# LDAQ-MOD-BREADBOARD.net
KiCad netlist of a schematic drawn in EAGLE
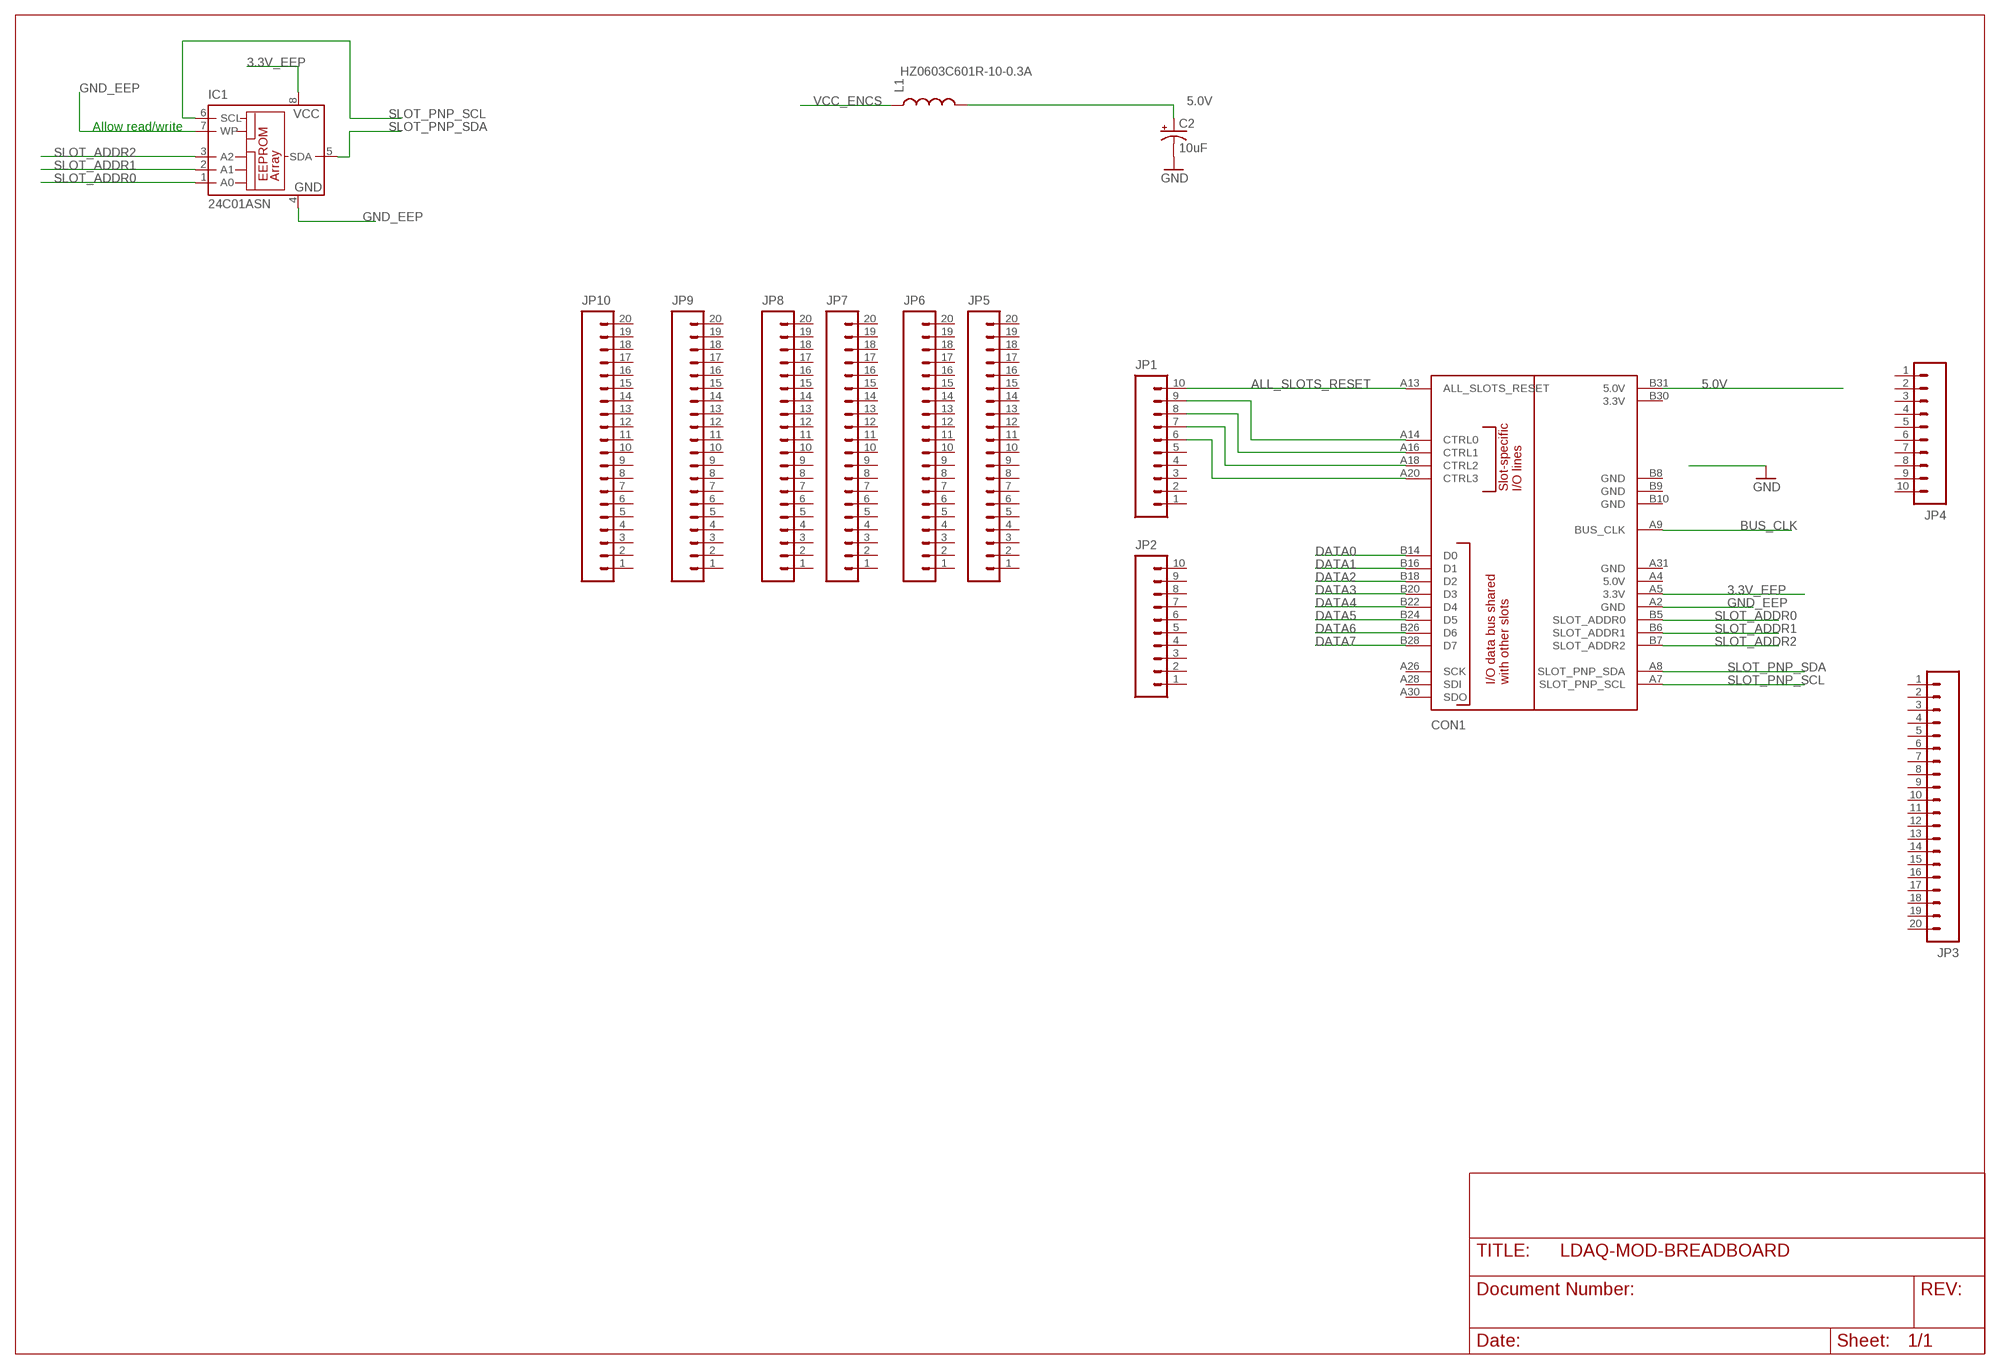
[diagram p0: schematic, sheet 1]

(export (version "E")
  (design (tool "Eeschema 10.0.6"))
  (components
    (comp (ref "C2")
      (value "10uF")
      (footprint "eagle-import:EIA3216")
      (libsource (lib "eagle-import") (part "CAP_POL1206"))
    )
    (comp (ref "CON1")
      (value "BOARD")
      (footprint "eagle-import:PCI-E_64_EDGE_70X60")
      (libsource (lib "eagle-import") (part "LIBREDAQ_DAUGHTER_BOARDPCIE-64_SIZE1"))
    )
    (comp (ref "IC1")
      (value "24C01ASN")
      (footprint "eagle-import:SO-08")
      (fields (field (name "MPN") "AT24C01BN-SH-B"))
      (libsource (lib "eagle-import") (part "24CSN01A"))
    )
    (comp (ref "JP1")
      (value "M10NO_SILK_PTH_FEMALE")
      (footprint "eagle-import:1X10_NO_SILK")
      (libsource (lib "eagle-import") (part "M10NO_SILK_PTH_FEMALE"))
    )
    (comp (ref "JP2")
      (value "M10NO_SILK_PTH_FEMALE")
      (footprint "eagle-import:1X10_NO_SILK")
      (libsource (lib "eagle-import") (part "M10NO_SILK_PTH_FEMALE"))
    )
    (comp (ref "JP3")
      (value "M20")
      (footprint "eagle-import:1X20")
      (libsource (lib "eagle-import") (part "M20"))
    )
    (comp (ref "JP4")
      (value "M10NO_SILK_PTH_FEMALE")
      (footprint "eagle-import:1X10_NO_SILK")
      (libsource (lib "eagle-import") (part "M10NO_SILK_PTH_FEMALE"))
    )
    (comp (ref "JP5")
      (value "M20")
      (footprint "eagle-import:1X20")
      (libsource (lib "eagle-import") (part "M20"))
    )
    (comp (ref "JP6")
      (value "M20")
      (footprint "eagle-import:1X20")
      (libsource (lib "eagle-import") (part "M20"))
    )
    (comp (ref "JP7")
      (value "M20")
      (footprint "eagle-import:1X20")
      (libsource (lib "eagle-import") (part "M20"))
    )
    (comp (ref "JP8")
      (value "M20")
      (footprint "eagle-import:1X20")
      (libsource (lib "eagle-import") (part "M20"))
    )
    (comp (ref "JP9")
      (value "M20")
      (footprint "eagle-import:1X20")
      (libsource (lib "eagle-import") (part "M20"))
    )
    (comp (ref "JP10")
      (value "M20")
      (footprint "eagle-import:1X20")
      (libsource (lib "eagle-import") (part "M20"))
    )
    (comp (ref "L1")
      (value "HZ0603C601R-10-0.3A")
      (footprint "eagle-import:0603")
      (libsource (lib "eagle-import") (part "INDUCTOR0603"))
    )
  )
  (nets
    (net (code "1") (name "/3.3V_EEP") (class "Default")
      (node (ref "CON1") (pin "A5") (pinfunction "3.3V_A5") (pintype "bidirectional"))
      (node (ref "IC1") (pin "8") (pinfunction "VCC_8") (pintype "power_in"))
    )
    (net (code "2") (name "/5.0V") (class "Default")
      (node (ref "C2") (pin "A") (pinfunction "+_A") (pintype "passive"))
      (node (ref "CON1") (pin "B31") (pinfunction "5.0V_B31") (pintype "bidirectional"))
      (node (ref "L1") (pin "2") (pinfunction "2_2") (pintype "passive"))
    )
    (net (code "3") (name "/ALL_SLOTS_RESET") (class "Default")
      (node (ref "CON1") (pin "A13") (pinfunction "ALL_SLOTS_RESET_A13") (pintype "bidirectional"))
      (node (ref "JP1") (pin "10") (pinfunction "10_10") (pintype "passive"))
    )
    (net (code "4") (name "/BUS_CLK") (class "Default")
      (node (ref "CON1") (pin "A9") (pinfunction "BUS_CLK_A9") (pintype "bidirectional"))
    )
    (net (code "5") (name "/DATA0") (class "Default")
      (node (ref "CON1") (pin "B14") (pinfunction "D0_B14") (pintype "bidirectional"))
    )
    (net (code "6") (name "/DATA1") (class "Default")
      (node (ref "CON1") (pin "B16") (pinfunction "D1_B16") (pintype "bidirectional"))
    )
    (net (code "7") (name "/DATA2") (class "Default")
      (node (ref "CON1") (pin "B18") (pinfunction "D2_B18") (pintype "bidirectional"))
    )
    (net (code "8") (name "/DATA3") (class "Default")
      (node (ref "CON1") (pin "B20") (pinfunction "D3_B20") (pintype "bidirectional"))
    )
    (net (code "9") (name "/DATA4") (class "Default")
      (node (ref "CON1") (pin "B22") (pinfunction "D4_B22") (pintype "bidirectional"))
    )
    (net (code "10") (name "/DATA5") (class "Default")
      (node (ref "CON1") (pin "B24") (pinfunction "D5_B24") (pintype "bidirectional"))
    )
    (net (code "11") (name "/DATA6") (class "Default")
      (node (ref "CON1") (pin "B26") (pinfunction "D6_B26") (pintype "bidirectional"))
    )
    (net (code "12") (name "/DATA7") (class "Default")
      (node (ref "CON1") (pin "B28") (pinfunction "D7_B28") (pintype "bidirectional"))
    )
    (net (code "13") (name "/GND_EEP") (class "Default")
      (node (ref "CON1") (pin "A2") (pinfunction "GND_A2") (pintype "bidirectional"))
      (node (ref "IC1") (pin "4") (pinfunction "GND_4") (pintype "power_in"))
      (node (ref "IC1") (pin "7") (pinfunction "WP_7") (pintype "input"))
    )
    (net (code "14") (name "/SLOT_ADDR0") (class "Default")
      (node (ref "CON1") (pin "B5") (pinfunction "SLOT_ADDR0_B5") (pintype "bidirectional"))
      (node (ref "IC1") (pin "1") (pinfunction "A0_1") (pintype "input"))
    )
    (net (code "15") (name "/SLOT_ADDR1") (class "Default")
      (node (ref "CON1") (pin "B6") (pinfunction "SLOT_ADDR1_B6") (pintype "bidirectional"))
      (node (ref "IC1") (pin "2") (pinfunction "A1_2") (pintype "input"))
    )
    (net (code "16") (name "/SLOT_ADDR2") (class "Default")
      (node (ref "CON1") (pin "B7") (pinfunction "SLOT_ADDR2_B7") (pintype "bidirectional"))
      (node (ref "IC1") (pin "3") (pinfunction "A2_3") (pintype "input"))
    )
    (net (code "17") (name "/SLOT_PNP_SCL") (class "Default")
      (node (ref "CON1") (pin "A7") (pinfunction "SLOT_PNP_SCL_A7") (pintype "bidirectional"))
      (node (ref "IC1") (pin "6") (pinfunction "SCL_6") (pintype "input"))
    )
    (net (code "18") (name "/SLOT_PNP_SDA") (class "Default")
      (node (ref "CON1") (pin "A8") (pinfunction "SLOT_PNP_SDA_A8") (pintype "bidirectional"))
      (node (ref "IC1") (pin "5") (pinfunction "SDA_5") (pintype "bidirectional"))
    )
    (net (code "19") (name "/VCC_ENCS") (class "Default")
      (node (ref "L1") (pin "1") (pinfunction "1_1") (pintype "passive"))
    )
    (net (code "20") (name "GND") (class "Default")
      (node (ref "C2") (pin "C") (pinfunction "-_C") (pintype "passive"))
    )
    (net (code "21") (name "Net-(CON1-CTRL0)") (class "Default")
      (node (ref "CON1") (pin "A14") (pinfunction "CTRL0_A14") (pintype "bidirectional"))
      (node (ref "JP1") (pin "9") (pinfunction "9_9") (pintype "passive"))
    )
    (net (code "22") (name "Net-(CON1-CTRL1)") (class "Default")
      (node (ref "CON1") (pin "A16") (pinfunction "CTRL1_A16") (pintype "bidirectional"))
      (node (ref "JP1") (pin "8") (pinfunction "8_8") (pintype "passive"))
    )
    (net (code "23") (name "Net-(CON1-CTRL2)") (class "Default")
      (node (ref "CON1") (pin "A18") (pinfunction "CTRL2_A18") (pintype "bidirectional"))
      (node (ref "JP1") (pin "7") (pinfunction "7_7") (pintype "passive"))
    )
    (net (code "24") (name "Net-(CON1-CTRL3)") (class "Default")
      (node (ref "CON1") (pin "A20") (pinfunction "CTRL3_A20") (pintype "bidirectional"))
      (node (ref "JP1") (pin "6") (pinfunction "6_6") (pintype "passive"))
    )
    (net (code "25") (name "unconnected-(CON1-3.3V-PadB30)") (class "Default")
      (node (ref "CON1") (pin "B30") (pinfunction "3.3V_B30") (pintype "bidirectional"))
    )
    (net (code "26") (name "unconnected-(CON1-5.0V-PadA4)") (class "Default")
      (node (ref "CON1") (pin "A4") (pinfunction "5.0V_A4") (pintype "bidirectional"))
    )
    (net (code "27") (name "unconnected-(CON1-GND-PadA31)") (class "Default")
      (node (ref "CON1") (pin "A31") (pinfunction "GND_A31") (pintype "bidirectional"))
    )
    (net (code "28") (name "unconnected-(CON1-GND-PadB8)") (class "Default")
      (node (ref "CON1") (pin "B8") (pinfunction "GND_B8") (pintype "bidirectional"))
    )
    (net (code "29") (name "unconnected-(CON1-GND-PadB9)") (class "Default")
      (node (ref "CON1") (pin "B9") (pinfunction "GND_B9") (pintype "bidirectional"))
    )
    (net (code "30") (name "unconnected-(CON1-GND-PadB10)") (class "Default")
      (node (ref "CON1") (pin "B10") (pinfunction "GND_B10") (pintype "bidirectional"))
    )
    (net (code "31") (name "unconnected-(CON1-SCK-PadA26)") (class "Default")
      (node (ref "CON1") (pin "A26") (pinfunction "SCK_A26") (pintype "bidirectional"))
    )
    (net (code "32") (name "unconnected-(CON1-SDI-PadA28)") (class "Default")
      (node (ref "CON1") (pin "A28") (pinfunction "SDI_A28") (pintype "bidirectional"))
    )
    (net (code "33") (name "unconnected-(CON1-SDO-PadA30)") (class "Default")
      (node (ref "CON1") (pin "A30") (pinfunction "SDO_A30") (pintype "bidirectional"))
    )
    (net (code "34") (name "unconnected-(JP1-Pad1)") (class "Default")
      (node (ref "JP1") (pin "1") (pinfunction "1_1") (pintype "passive"))
    )
    (net (code "35") (name "unconnected-(JP1-Pad2)") (class "Default")
      (node (ref "JP1") (pin "2") (pinfunction "2_2") (pintype "passive"))
    )
    (net (code "36") (name "unconnected-(JP1-Pad3)") (class "Default")
      (node (ref "JP1") (pin "3") (pinfunction "3_3") (pintype "passive"))
    )
    (net (code "37") (name "unconnected-(JP1-Pad4)") (class "Default")
      (node (ref "JP1") (pin "4") (pinfunction "4_4") (pintype "passive"))
    )
    (net (code "38") (name "unconnected-(JP1-Pad5)") (class "Default")
      (node (ref "JP1") (pin "5") (pinfunction "5_5") (pintype "passive"))
    )
    (net (code "39") (name "unconnected-(JP2-Pad1)") (class "Default")
      (node (ref "JP2") (pin "1") (pinfunction "1_1") (pintype "passive"))
    )
    (net (code "40") (name "unconnected-(JP2-Pad2)") (class "Default")
      (node (ref "JP2") (pin "2") (pinfunction "2_2") (pintype "passive"))
    )
    (net (code "41") (name "unconnected-(JP2-Pad3)") (class "Default")
      (node (ref "JP2") (pin "3") (pinfunction "3_3") (pintype "passive"))
    )
    (net (code "42") (name "unconnected-(JP2-Pad4)") (class "Default")
      (node (ref "JP2") (pin "4") (pinfunction "4_4") (pintype "passive"))
    )
    (net (code "43") (name "unconnected-(JP2-Pad5)") (class "Default")
      (node (ref "JP2") (pin "5") (pinfunction "5_5") (pintype "passive"))
    )
    (net (code "44") (name "unconnected-(JP2-Pad6)") (class "Default")
      (node (ref "JP2") (pin "6") (pinfunction "6_6") (pintype "passive"))
    )
    (net (code "45") (name "unconnected-(JP2-Pad7)") (class "Default")
      (node (ref "JP2") (pin "7") (pinfunction "7_7") (pintype "passive"))
    )
    (net (code "46") (name "unconnected-(JP2-Pad8)") (class "Default")
      (node (ref "JP2") (pin "8") (pinfunction "8_8") (pintype "passive"))
    )
    (net (code "47") (name "unconnected-(JP2-Pad9)") (class "Default")
      (node (ref "JP2") (pin "9") (pinfunction "9_9") (pintype "passive"))
    )
    (net (code "48") (name "unconnected-(JP2-Pad10)") (class "Default")
      (node (ref "JP2") (pin "10") (pinfunction "10_10") (pintype "passive"))
    )
    (net (code "49") (name "unconnected-(JP3-Pad1)") (class "Default")
      (node (ref "JP3") (pin "1") (pinfunction "1_1") (pintype "passive"))
    )
    (net (code "50") (name "unconnected-(JP3-Pad2)") (class "Default")
      (node (ref "JP3") (pin "2") (pinfunction "2_2") (pintype "passive"))
    )
    (net (code "51") (name "unconnected-(JP3-Pad3)") (class "Default")
      (node (ref "JP3") (pin "3") (pinfunction "3_3") (pintype "passive"))
    )
    (net (code "52") (name "unconnected-(JP3-Pad4)") (class "Default")
      (node (ref "JP3") (pin "4") (pinfunction "4_4") (pintype "passive"))
    )
    (net (code "53") (name "unconnected-(JP3-Pad5)") (class "Default")
      (node (ref "JP3") (pin "5") (pinfunction "5_5") (pintype "passive"))
    )
    (net (code "54") (name "unconnected-(JP3-Pad6)") (class "Default")
      (node (ref "JP3") (pin "6") (pinfunction "6_6") (pintype "passive"))
    )
    (net (code "55") (name "unconnected-(JP3-Pad7)") (class "Default")
      (node (ref "JP3") (pin "7") (pinfunction "7_7") (pintype "passive"))
    )
    (net (code "56") (name "unconnected-(JP3-Pad8)") (class "Default")
      (node (ref "JP3") (pin "8") (pinfunction "8_8") (pintype "passive"))
    )
    (net (code "57") (name "unconnected-(JP3-Pad9)") (class "Default")
      (node (ref "JP3") (pin "9") (pinfunction "9_9") (pintype "passive"))
    )
    (net (code "58") (name "unconnected-(JP3-Pad10)") (class "Default")
      (node (ref "JP3") (pin "10") (pinfunction "10_10") (pintype "passive"))
    )
    (net (code "59") (name "unconnected-(JP3-Pad11)") (class "Default")
      (node (ref "JP3") (pin "11") (pinfunction "11_11") (pintype "passive"))
    )
    (net (code "60") (name "unconnected-(JP3-Pad12)") (class "Default")
      (node (ref "JP3") (pin "12") (pinfunction "12_12") (pintype "passive"))
    )
    (net (code "61") (name "unconnected-(JP3-Pad13)") (class "Default")
      (node (ref "JP3") (pin "13") (pinfunction "13_13") (pintype "passive"))
    )
    (net (code "62") (name "unconnected-(JP3-Pad14)") (class "Default")
      (node (ref "JP3") (pin "14") (pinfunction "14_14") (pintype "passive"))
    )
    (net (code "63") (name "unconnected-(JP3-Pad15)") (class "Default")
      (node (ref "JP3") (pin "15") (pinfunction "15_15") (pintype "passive"))
    )
    (net (code "64") (name "unconnected-(JP3-Pad16)") (class "Default")
      (node (ref "JP3") (pin "16") (pinfunction "16_16") (pintype "passive"))
    )
    (net (code "65") (name "unconnected-(JP3-Pad17)") (class "Default")
      (node (ref "JP3") (pin "17") (pinfunction "17_17") (pintype "passive"))
    )
    (net (code "66") (name "unconnected-(JP3-Pad18)") (class "Default")
      (node (ref "JP3") (pin "18") (pinfunction "18_18") (pintype "passive"))
    )
    (net (code "67") (name "unconnected-(JP3-Pad19)") (class "Default")
      (node (ref "JP3") (pin "19") (pinfunction "19_19") (pintype "passive"))
    )
    (net (code "68") (name "unconnected-(JP3-Pad20)") (class "Default")
      (node (ref "JP3") (pin "20") (pinfunction "20_20") (pintype "passive"))
    )
    (net (code "69") (name "unconnected-(JP4-Pad1)") (class "Default")
      (node (ref "JP4") (pin "1") (pinfunction "1_1") (pintype "passive"))
    )
    (net (code "70") (name "unconnected-(JP4-Pad2)") (class "Default")
      (node (ref "JP4") (pin "2") (pinfunction "2_2") (pintype "passive"))
    )
    (net (code "71") (name "unconnected-(JP4-Pad3)") (class "Default")
      (node (ref "JP4") (pin "3") (pinfunction "3_3") (pintype "passive"))
    )
    (net (code "72") (name "unconnected-(JP4-Pad4)") (class "Default")
      (node (ref "JP4") (pin "4") (pinfunction "4_4") (pintype "passive"))
    )
    (net (code "73") (name "unconnected-(JP4-Pad5)") (class "Default")
      (node (ref "JP4") (pin "5") (pinfunction "5_5") (pintype "passive"))
    )
    (net (code "74") (name "unconnected-(JP4-Pad6)") (class "Default")
      (node (ref "JP4") (pin "6") (pinfunction "6_6") (pintype "passive"))
    )
    (net (code "75") (name "unconnected-(JP4-Pad7)") (class "Default")
      (node (ref "JP4") (pin "7") (pinfunction "7_7") (pintype "passive"))
    )
    (net (code "76") (name "unconnected-(JP4-Pad8)") (class "Default")
      (node (ref "JP4") (pin "8") (pinfunction "8_8") (pintype "passive"))
    )
    (net (code "77") (name "unconnected-(JP4-Pad9)") (class "Default")
      (node (ref "JP4") (pin "9") (pinfunction "9_9") (pintype "passive"))
    )
    (net (code "78") (name "unconnected-(JP4-Pad10)") (class "Default")
      (node (ref "JP4") (pin "10") (pinfunction "10_10") (pintype "passive"))
    )
    (net (code "79") (name "unconnected-(JP5-Pad1)") (class "Default")
      (node (ref "JP5") (pin "1") (pinfunction "1_1") (pintype "passive"))
    )
    (net (code "80") (name "unconnected-(JP5-Pad2)") (class "Default")
      (node (ref "JP5") (pin "2") (pinfunction "2_2") (pintype "passive"))
    )
    (net (code "81") (name "unconnected-(JP5-Pad3)") (class "Default")
      (node (ref "JP5") (pin "3") (pinfunction "3_3") (pintype "passive"))
    )
    (net (code "82") (name "unconnected-(JP5-Pad4)") (class "Default")
      (node (ref "JP5") (pin "4") (pinfunction "4_4") (pintype "passive"))
    )
    (net (code "83") (name "unconnected-(JP5-Pad5)") (class "Default")
      (node (ref "JP5") (pin "5") (pinfunction "5_5") (pintype "passive"))
    )
    (net (code "84") (name "unconnected-(JP5-Pad6)") (class "Default")
      (node (ref "JP5") (pin "6") (pinfunction "6_6") (pintype "passive"))
    )
    (net (code "85") (name "unconnected-(JP5-Pad7)") (class "Default")
      (node (ref "JP5") (pin "7") (pinfunction "7_7") (pintype "passive"))
    )
    (net (code "86") (name "unconnected-(JP5-Pad8)") (class "Default")
      (node (ref "JP5") (pin "8") (pinfunction "8_8") (pintype "passive"))
    )
    (net (code "87") (name "unconnected-(JP5-Pad9)") (class "Default")
      (node (ref "JP5") (pin "9") (pinfunction "9_9") (pintype "passive"))
    )
    (net (code "88") (name "unconnected-(JP5-Pad10)") (class "Default")
      (node (ref "JP5") (pin "10") (pinfunction "10_10") (pintype "passive"))
    )
    (net (code "89") (name "unconnected-(JP5-Pad11)") (class "Default")
      (node (ref "JP5") (pin "11") (pinfunction "11_11") (pintype "passive"))
    )
    (net (code "90") (name "unconnected-(JP5-Pad12)") (class "Default")
      (node (ref "JP5") (pin "12") (pinfunction "12_12") (pintype "passive"))
    )
    (net (code "91") (name "unconnected-(JP5-Pad13)") (class "Default")
      (node (ref "JP5") (pin "13") (pinfunction "13_13") (pintype "passive"))
    )
    (net (code "92") (name "unconnected-(JP5-Pad14)") (class "Default")
      (node (ref "JP5") (pin "14") (pinfunction "14_14") (pintype "passive"))
    )
    (net (code "93") (name "unconnected-(JP5-Pad15)") (class "Default")
      (node (ref "JP5") (pin "15") (pinfunction "15_15") (pintype "passive"))
    )
    (net (code "94") (name "unconnected-(JP5-Pad16)") (class "Default")
      (node (ref "JP5") (pin "16") (pinfunction "16_16") (pintype "passive"))
    )
    (net (code "95") (name "unconnected-(JP5-Pad17)") (class "Default")
      (node (ref "JP5") (pin "17") (pinfunction "17_17") (pintype "passive"))
    )
    (net (code "96") (name "unconnected-(JP5-Pad18)") (class "Default")
      (node (ref "JP5") (pin "18") (pinfunction "18_18") (pintype "passive"))
    )
    (net (code "97") (name "unconnected-(JP5-Pad19)") (class "Default")
      (node (ref "JP5") (pin "19") (pinfunction "19_19") (pintype "passive"))
    )
    (net (code "98") (name "unconnected-(JP5-Pad20)") (class "Default")
      (node (ref "JP5") (pin "20") (pinfunction "20_20") (pintype "passive"))
    )
    (net (code "99") (name "unconnected-(JP6-Pad1)") (class "Default")
      (node (ref "JP6") (pin "1") (pinfunction "1_1") (pintype "passive"))
    )
    (net (code "100") (name "unconnected-(JP6-Pad2)") (class "Default")
      (node (ref "JP6") (pin "2") (pinfunction "2_2") (pintype "passive"))
    )
    (net (code "101") (name "unconnected-(JP6-Pad3)") (class "Default")
      (node (ref "JP6") (pin "3") (pinfunction "3_3") (pintype "passive"))
    )
    (net (code "102") (name "unconnected-(JP6-Pad4)") (class "Default")
      (node (ref "JP6") (pin "4") (pinfunction "4_4") (pintype "passive"))
    )
    (net (code "103") (name "unconnected-(JP6-Pad5)") (class "Default")
      (node (ref "JP6") (pin "5") (pinfunction "5_5") (pintype "passive"))
    )
    (net (code "104") (name "unconnected-(JP6-Pad6)") (class "Default")
      (node (ref "JP6") (pin "6") (pinfunction "6_6") (pintype "passive"))
    )
    (net (code "105") (name "unconnected-(JP6-Pad7)") (class "Default")
      (node (ref "JP6") (pin "7") (pinfunction "7_7") (pintype "passive"))
    )
    (net (code "106") (name "unconnected-(JP6-Pad8)") (class "Default")
      (node (ref "JP6") (pin "8") (pinfunction "8_8") (pintype "passive"))
    )
    (net (code "107") (name "unconnected-(JP6-Pad9)") (class "Default")
      (node (ref "JP6") (pin "9") (pinfunction "9_9") (pintype "passive"))
    )
    (net (code "108") (name "unconnected-(JP6-Pad10)") (class "Default")
      (node (ref "JP6") (pin "10") (pinfunction "10_10") (pintype "passive"))
    )
    (net (code "109") (name "unconnected-(JP6-Pad11)") (class "Default")
      (node (ref "JP6") (pin "11") (pinfunction "11_11") (pintype "passive"))
    )
    (net (code "110") (name "unconnected-(JP6-Pad12)") (class "Default")
      (node (ref "JP6") (pin "12") (pinfunction "12_12") (pintype "passive"))
    )
    (net (code "111") (name "unconnected-(JP6-Pad13)") (class "Default")
      (node (ref "JP6") (pin "13") (pinfunction "13_13") (pintype "passive"))
    )
    (net (code "112") (name "unconnected-(JP6-Pad14)") (class "Default")
      (node (ref "JP6") (pin "14") (pinfunction "14_14") (pintype "passive"))
    )
    (net (code "113") (name "unconnected-(JP6-Pad15)") (class "Default")
      (node (ref "JP6") (pin "15") (pinfunction "15_15") (pintype "passive"))
    )
    (net (code "114") (name "unconnected-(JP6-Pad16)") (class "Default")
      (node (ref "JP6") (pin "16") (pinfunction "16_16") (pintype "passive"))
    )
    (net (code "115") (name "unconnected-(JP6-Pad17)") (class "Default")
      (node (ref "JP6") (pin "17") (pinfunction "17_17") (pintype "passive"))
    )
    (net (code "116") (name "unconnected-(JP6-Pad18)") (class "Default")
      (node (ref "JP6") (pin "18") (pinfunction "18_18") (pintype "passive"))
    )
    (net (code "117") (name "unconnected-(JP6-Pad19)") (class "Default")
      (node (ref "JP6") (pin "19") (pinfunction "19_19") (pintype "passive"))
    )
    (net (code "118") (name "unconnected-(JP6-Pad20)") (class "Default")
      (node (ref "JP6") (pin "20") (pinfunction "20_20") (pintype "passive"))
    )
    (net (code "119") (name "unconnected-(JP7-Pad1)") (class "Default")
      (node (ref "JP7") (pin "1") (pinfunction "1_1") (pintype "passive"))
    )
    (net (code "120") (name "unconnected-(JP7-Pad2)") (class "Default")
      (node (ref "JP7") (pin "2") (pinfunction "2_2") (pintype "passive"))
    )
    (net (code "121") (name "unconnected-(JP7-Pad3)") (class "Default")
      (node (ref "JP7") (pin "3") (pinfunction "3_3") (pintype "passive"))
    )
    (net (code "122") (name "unconnected-(JP7-Pad4)") (class "Default")
      (node (ref "JP7") (pin "4") (pinfunction "4_4") (pintype "passive"))
    )
    (net (code "123") (name "unconnected-(JP7-Pad5)") (class "Default")
      (node (ref "JP7") (pin "5") (pinfunction "5_5") (pintype "passive"))
    )
    (net (code "124") (name "unconnected-(JP7-Pad6)") (class "Default")
      (node (ref "JP7") (pin "6") (pinfunction "6_6") (pintype "passive"))
    )
    (net (code "125") (name "unconnected-(JP7-Pad7)") (class "Default")
      (node (ref "JP7") (pin "7") (pinfunction "7_7") (pintype "passive"))
    )
    (net (code "126") (name "unconnected-(JP7-Pad8)") (class "Default")
      (node (ref "JP7") (pin "8") (pinfunction "8_8") (pintype "passive"))
    )
    (net (code "127") (name "unconnected-(JP7-Pad9)") (class "Default")
      (node (ref "JP7") (pin "9") (pinfunction "9_9") (pintype "passive"))
    )
    (net (code "128") (name "unconnected-(JP7-Pad10)") (class "Default")
      (node (ref "JP7") (pin "10") (pinfunction "10_10") (pintype "passive"))
    )
    (net (code "129") (name "unconnected-(JP7-Pad11)") (class "Default")
      (node (ref "JP7") (pin "11") (pinfunction "11_11") (pintype "passive"))
    )
    (net (code "130") (name "unconnected-(JP7-Pad12)") (class "Default")
      (node (ref "JP7") (pin "12") (pinfunction "12_12") (pintype "passive"))
    )
    (net (code "131") (name "unconnected-(JP7-Pad13)") (class "Default")
      (node (ref "JP7") (pin "13") (pinfunction "13_13") (pintype "passive"))
    )
    (net (code "132") (name "unconnected-(JP7-Pad14)") (class "Default")
      (node (ref "JP7") (pin "14") (pinfunction "14_14") (pintype "passive"))
    )
    (net (code "133") (name "unconnected-(JP7-Pad15)") (class "Default")
      (node (ref "JP7") (pin "15") (pinfunction "15_15") (pintype "passive"))
    )
    (net (code "134") (name "unconnected-(JP7-Pad16)") (class "Default")
      (node (ref "JP7") (pin "16") (pinfunction "16_16") (pintype "passive"))
    )
    (net (code "135") (name "unconnected-(JP7-Pad17)") (class "Default")
      (node (ref "JP7") (pin "17") (pinfunction "17_17") (pintype "passive"))
    )
    (net (code "136") (name "unconnected-(JP7-Pad18)") (class "Default")
      (node (ref "JP7") (pin "18") (pinfunction "18_18") (pintype "passive"))
    )
    (net (code "137") (name "unconnected-(JP7-Pad19)") (class "Default")
      (node (ref "JP7") (pin "19") (pinfunction "19_19") (pintype "passive"))
    )
    (net (code "138") (name "unconnected-(JP7-Pad20)") (class "Default")
      (node (ref "JP7") (pin "20") (pinfunction "20_20") (pintype "passive"))
    )
    (net (code "139") (name "unconnected-(JP8-Pad1)") (class "Default")
      (node (ref "JP8") (pin "1") (pinfunction "1_1") (pintype "passive"))
    )
    (net (code "140") (name "unconnected-(JP8-Pad2)") (class "Default")
      (node (ref "JP8") (pin "2") (pinfunction "2_2") (pintype "passive"))
    )
    (net (code "141") (name "unconnected-(JP8-Pad3)") (class "Default")
      (node (ref "JP8") (pin "3") (pinfunction "3_3") (pintype "passive"))
    )
    (net (code "142") (name "unconnected-(JP8-Pad4)") (class "Default")
      (node (ref "JP8") (pin "4") (pinfunction "4_4") (pintype "passive"))
    )
    (net (code "143") (name "unconnected-(JP8-Pad5)") (class "Default")
      (node (ref "JP8") (pin "5") (pinfunction "5_5") (pintype "passive"))
    )
    (net (code "144") (name "unconnected-(JP8-Pad6)") (class "Default")
      (node (ref "JP8") (pin "6") (pinfunction "6_6") (pintype "passive"))
    )
    (net (code "145") (name "unconnected-(JP8-Pad7)") (class "Default")
      (node (ref "JP8") (pin "7") (pinfunction "7_7") (pintype "passive"))
    )
    (net (code "146") (name "unconnected-(JP8-Pad8)") (class "Default")
      (node (ref "JP8") (pin "8") (pinfunction "8_8") (pintype "passive"))
    )
    (net (code "147") (name "unconnected-(JP8-Pad9)") (class "Default")
      (node (ref "JP8") (pin "9") (pinfunction "9_9") (pintype "passive"))
    )
    (net (code "148") (name "unconnected-(JP8-Pad10)") (class "Default")
      (node (ref "JP8") (pin "10") (pinfunction "10_10") (pintype "passive"))
    )
    (net (code "149") (name "unconnected-(JP8-Pad11)") (class "Default")
      (node (ref "JP8") (pin "11") (pinfunction "11_11") (pintype "passive"))
    )
    (net (code "150") (name "unconnected-(JP8-Pad12)") (class "Default")
      (node (ref "JP8") (pin "12") (pinfunction "12_12") (pintype "passive"))
    )
    (net (code "151") (name "unconnected-(JP8-Pad13)") (class "Default")
      (node (ref "JP8") (pin "13") (pinfunction "13_13") (pintype "passive"))
    )
    (net (code "152") (name "unconnected-(JP8-Pad14)") (class "Default")
      (node (ref "JP8") (pin "14") (pinfunction "14_14") (pintype "passive"))
    )
    (net (code "153") (name "unconnected-(JP8-Pad15)") (class "Default")
      (node (ref "JP8") (pin "15") (pinfunction "15_15") (pintype "passive"))
    )
    (net (code "154") (name "unconnected-(JP8-Pad16)") (class "Default")
      (node (ref "JP8") (pin "16") (pinfunction "16_16") (pintype "passive"))
    )
    (net (code "155") (name "unconnected-(JP8-Pad17)") (class "Default")
      (node (ref "JP8") (pin "17") (pinfunction "17_17") (pintype "passive"))
    )
    (net (code "156") (name "unconnected-(JP8-Pad18)") (class "Default")
      (node (ref "JP8") (pin "18") (pinfunction "18_18") (pintype "passive"))
    )
    (net (code "157") (name "unconnected-(JP8-Pad19)") (class "Default")
      (node (ref "JP8") (pin "19") (pinfunction "19_19") (pintype "passive"))
    )
    (net (code "158") (name "unconnected-(JP8-Pad20)") (class "Default")
      (node (ref "JP8") (pin "20") (pinfunction "20_20") (pintype "passive"))
    )
    (net (code "159") (name "unconnected-(JP9-Pad1)") (class "Default")
      (node (ref "JP9") (pin "1") (pinfunction "1_1") (pintype "passive"))
    )
    (net (code "160") (name "unconnected-(JP9-Pad2)") (class "Default")
      (node (ref "JP9") (pin "2") (pinfunction "2_2") (pintype "passive"))
    )
    (net (code "161") (name "unconnected-(JP9-Pad3)") (class "Default")
      (node (ref "JP9") (pin "3") (pinfunction "3_3") (pintype "passive"))
    )
    (net (code "162") (name "unconnected-(JP9-Pad4)") (class "Default")
      (node (ref "JP9") (pin "4") (pinfunction "4_4") (pintype "passive"))
    )
    (net (code "163") (name "unconnected-(JP9-Pad5)") (class "Default")
      (node (ref "JP9") (pin "5") (pinfunction "5_5") (pintype "passive"))
    )
    (net (code "164") (name "unconnected-(JP9-Pad6)") (class "Default")
      (node (ref "JP9") (pin "6") (pinfunction "6_6") (pintype "passive"))
    )
    (net (code "165") (name "unconnected-(JP9-Pad7)") (class "Default")
      (node (ref "JP9") (pin "7") (pinfunction "7_7") (pintype "passive"))
    )
    (net (code "166") (name "unconnected-(JP9-Pad8)") (class "Default")
      (node (ref "JP9") (pin "8") (pinfunction "8_8") (pintype "passive"))
    )
    (net (code "167") (name "unconnected-(JP9-Pad9)") (class "Default")
      (node (ref "JP9") (pin "9") (pinfunction "9_9") (pintype "passive"))
    )
    (net (code "168") (name "unconnected-(JP9-Pad10)") (class "Default")
      (node (ref "JP9") (pin "10") (pinfunction "10_10") (pintype "passive"))
    )
    (net (code "169") (name "unconnected-(JP9-Pad11)") (class "Default")
      (node (ref "JP9") (pin "11") (pinfunction "11_11") (pintype "passive"))
    )
    (net (code "170") (name "unconnected-(JP9-Pad12)") (class "Default")
      (node (ref "JP9") (pin "12") (pinfunction "12_12") (pintype "passive"))
    )
    (net (code "171") (name "unconnected-(JP9-Pad13)") (class "Default")
      (node (ref "JP9") (pin "13") (pinfunction "13_13") (pintype "passive"))
    )
    (net (code "172") (name "unconnected-(JP9-Pad14)") (class "Default")
      (node (ref "JP9") (pin "14") (pinfunction "14_14") (pintype "passive"))
    )
    (net (code "173") (name "unconnected-(JP9-Pad15)") (class "Default")
      (node (ref "JP9") (pin "15") (pinfunction "15_15") (pintype "passive"))
    )
    (net (code "174") (name "unconnected-(JP9-Pad16)") (class "Default")
      (node (ref "JP9") (pin "16") (pinfunction "16_16") (pintype "passive"))
    )
    (net (code "175") (name "unconnected-(JP9-Pad17)") (class "Default")
      (node (ref "JP9") (pin "17") (pinfunction "17_17") (pintype "passive"))
    )
    (net (code "176") (name "unconnected-(JP9-Pad18)") (class "Default")
      (node (ref "JP9") (pin "18") (pinfunction "18_18") (pintype "passive"))
    )
    (net (code "177") (name "unconnected-(JP9-Pad19)") (class "Default")
      (node (ref "JP9") (pin "19") (pinfunction "19_19") (pintype "passive"))
    )
    (net (code "178") (name "unconnected-(JP9-Pad20)") (class "Default")
      (node (ref "JP9") (pin "20") (pinfunction "20_20") (pintype "passive"))
    )
    (net (code "179") (name "unconnected-(JP10-Pad1)") (class "Default")
      (node (ref "JP10") (pin "1") (pinfunction "1_1") (pintype "passive"))
    )
    (net (code "180") (name "unconnected-(JP10-Pad2)") (class "Default")
      (node (ref "JP10") (pin "2") (pinfunction "2_2") (pintype "passive"))
    )
    (net (code "181") (name "unconnected-(JP10-Pad3)") (class "Default")
      (node (ref "JP10") (pin "3") (pinfunction "3_3") (pintype "passive"))
    )
    (net (code "182") (name "unconnected-(JP10-Pad4)") (class "Default")
      (node (ref "JP10") (pin "4") (pinfunction "4_4") (pintype "passive"))
    )
    (net (code "183") (name "unconnected-(JP10-Pad5)") (class "Default")
      (node (ref "JP10") (pin "5") (pinfunction "5_5") (pintype "passive"))
    )
    (net (code "184") (name "unconnected-(JP10-Pad6)") (class "Default")
      (node (ref "JP10") (pin "6") (pinfunction "6_6") (pintype "passive"))
    )
    (net (code "185") (name "unconnected-(JP10-Pad7)") (class "Default")
      (node (ref "JP10") (pin "7") (pinfunction "7_7") (pintype "passive"))
    )
    (net (code "186") (name "unconnected-(JP10-Pad8)") (class "Default")
      (node (ref "JP10") (pin "8") (pinfunction "8_8") (pintype "passive"))
    )
    (net (code "187") (name "unconnected-(JP10-Pad9)") (class "Default")
      (node (ref "JP10") (pin "9") (pinfunction "9_9") (pintype "passive"))
    )
    (net (code "188") (name "unconnected-(JP10-Pad10)") (class "Default")
      (node (ref "JP10") (pin "10") (pinfunction "10_10") (pintype "passive"))
    )
    (net (code "189") (name "unconnected-(JP10-Pad11)") (class "Default")
      (node (ref "JP10") (pin "11") (pinfunction "11_11") (pintype "passive"))
    )
    (net (code "190") (name "unconnected-(JP10-Pad12)") (class "Default")
      (node (ref "JP10") (pin "12") (pinfunction "12_12") (pintype "passive"))
    )
    (net (code "191") (name "unconnected-(JP10-Pad13)") (class "Default")
      (node (ref "JP10") (pin "13") (pinfunction "13_13") (pintype "passive"))
    )
    (net (code "192") (name "unconnected-(JP10-Pad14)") (class "Default")
      (node (ref "JP10") (pin "14") (pinfunction "14_14") (pintype "passive"))
    )
    (net (code "193") (name "unconnected-(JP10-Pad15)") (class "Default")
      (node (ref "JP10") (pin "15") (pinfunction "15_15") (pintype "passive"))
    )
    (net (code "194") (name "unconnected-(JP10-Pad16)") (class "Default")
      (node (ref "JP10") (pin "16") (pinfunction "16_16") (pintype "passive"))
    )
    (net (code "195") (name "unconnected-(JP10-Pad17)") (class "Default")
      (node (ref "JP10") (pin "17") (pinfunction "17_17") (pintype "passive"))
    )
    (net (code "196") (name "unconnected-(JP10-Pad18)") (class "Default")
      (node (ref "JP10") (pin "18") (pinfunction "18_18") (pintype "passive"))
    )
    (net (code "197") (name "unconnected-(JP10-Pad19)") (class "Default")
      (node (ref "JP10") (pin "19") (pinfunction "19_19") (pintype "passive"))
    )
    (net (code "198") (name "unconnected-(JP10-Pad20)") (class "Default")
      (node (ref "JP10") (pin "20") (pinfunction "20_20") (pintype "passive"))
    )
  )
)
